# EtherWiz_FullSize.net
KiCad netlist of a schematic drawn in Altium Designer
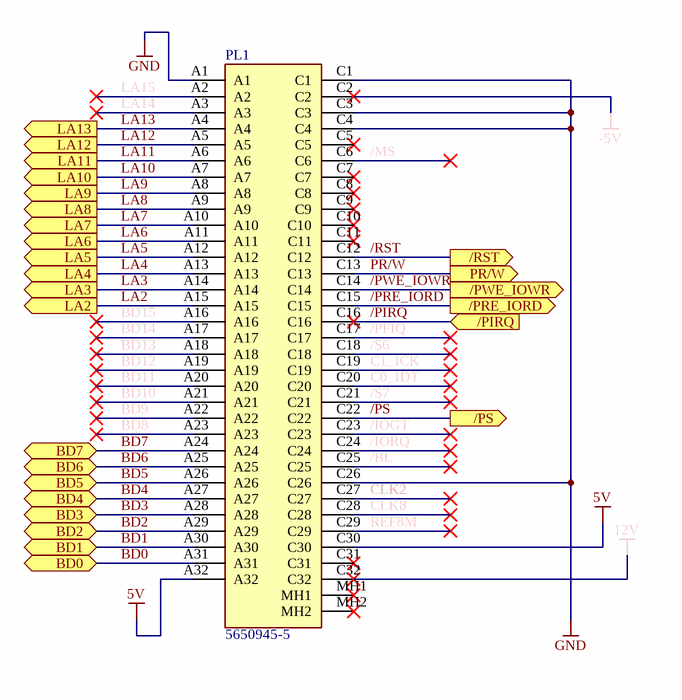
[diagram p0: EtherWiz_FullSize.SchDoc]

(export (version "E")
  (design (tool "Eeschema 10.0.6"))
  (components
    (comp (ref "PL1")
      (value "5650945-5")
      (footprint "SamacSys:56509455")
      (description "Connector")
      (fields (field (name "MOUSER PART NUMBER") "571-5650945-5"))
      (libsource (lib "Acorn") (part "5650945-5"))
    )
  )
  (nets
    (net (code "1") (name "-5V") (class "Default")
      (node (ref "PL1") (pin "C2") (pinfunction "C2_C2") (pintype "passive"))
    )
    (net (code "2") (name "/BD0") (class "Default")
      (node (ref "PL1") (pin "A31") (pinfunction "A31_A31") (pintype "passive"))
    )
    (net (code "3") (name "/BD1") (class "Default")
      (node (ref "PL1") (pin "A30") (pinfunction "A30_A30") (pintype "passive"))
    )
    (net (code "4") (name "/BD2") (class "Default")
      (node (ref "PL1") (pin "A29") (pinfunction "A29_A29") (pintype "passive"))
    )
    (net (code "5") (name "/BD3") (class "Default")
      (node (ref "PL1") (pin "A28") (pinfunction "A28_A28") (pintype "passive"))
    )
    (net (code "6") (name "/BD4") (class "Default")
      (node (ref "PL1") (pin "A27") (pinfunction "A27_A27") (pintype "passive"))
    )
    (net (code "7") (name "/BD5") (class "Default")
      (node (ref "PL1") (pin "A26") (pinfunction "A26_A26") (pintype "passive"))
    )
    (net (code "8") (name "/BD6") (class "Default")
      (node (ref "PL1") (pin "A25") (pinfunction "A25_A25") (pintype "passive"))
    )
    (net (code "9") (name "/BD7") (class "Default")
      (node (ref "PL1") (pin "A24") (pinfunction "A24_A24") (pintype "passive"))
    )
    (net (code "10") (name "/BD8") (class "Default")
      (node (ref "PL1") (pin "A23") (pinfunction "A23_A23") (pintype "passive+no_connect"))
    )
    (net (code "11") (name "/BD9") (class "Default")
      (node (ref "PL1") (pin "A22") (pinfunction "A22_A22") (pintype "passive+no_connect"))
    )
    (net (code "12") (name "/BD10") (class "Default")
      (node (ref "PL1") (pin "A21") (pinfunction "A21_A21") (pintype "passive+no_connect"))
    )
    (net (code "13") (name "/BD11") (class "Default")
      (node (ref "PL1") (pin "A20") (pinfunction "A20_A20") (pintype "passive+no_connect"))
    )
    (net (code "14") (name "/BD12") (class "Default")
      (node (ref "PL1") (pin "A19") (pinfunction "A19_A19") (pintype "passive+no_connect"))
    )
    (net (code "15") (name "/BD13") (class "Default")
      (node (ref "PL1") (pin "A18") (pinfunction "A18_A18") (pintype "passive+no_connect"))
    )
    (net (code "16") (name "/BD14") (class "Default")
      (node (ref "PL1") (pin "A17") (pinfunction "A17_A17") (pintype "passive+no_connect"))
    )
    (net (code "17") (name "/BD15") (class "Default")
      (node (ref "PL1") (pin "A16") (pinfunction "A16_A16") (pintype "passive+no_connect"))
    )
    (net (code "18") (name "/C0_IDT") (class "Default")
      (node (ref "PL1") (pin "C20") (pinfunction "C20_C20") (pintype "passive+no_connect"))
    )
    (net (code "19") (name "/C1_ICK") (class "Default")
      (node (ref "PL1") (pin "C19") (pinfunction "C19_C19") (pintype "passive+no_connect"))
    )
    (net (code "20") (name "/CLK2") (class "Default")
      (node (ref "PL1") (pin "C27") (pinfunction "C27_C27") (pintype "passive+no_connect"))
    )
    (net (code "21") (name "/CLK8") (class "Default")
      (node (ref "PL1") (pin "C28") (pinfunction "C28_C28") (pintype "passive+no_connect"))
    )
    (net (code "22") (name "/LA2") (class "Default")
      (node (ref "PL1") (pin "A15") (pinfunction "A15_A15") (pintype "passive"))
    )
    (net (code "23") (name "/LA3") (class "Default")
      (node (ref "PL1") (pin "A14") (pinfunction "A14_A14") (pintype "passive"))
    )
    (net (code "24") (name "/LA4") (class "Default")
      (node (ref "PL1") (pin "A13") (pinfunction "A13_A13") (pintype "passive"))
    )
    (net (code "25") (name "/LA5") (class "Default")
      (node (ref "PL1") (pin "A12") (pinfunction "A12_A12") (pintype "passive"))
    )
    (net (code "26") (name "/LA6") (class "Default")
      (node (ref "PL1") (pin "A11") (pinfunction "A11_A11") (pintype "passive"))
    )
    (net (code "27") (name "/LA7") (class "Default")
      (node (ref "PL1") (pin "A10") (pinfunction "A10_A10") (pintype "passive"))
    )
    (net (code "28") (name "/LA8") (class "Default")
      (node (ref "PL1") (pin "A9") (pinfunction "A9_A9") (pintype "passive"))
    )
    (net (code "29") (name "/LA9") (class "Default")
      (node (ref "PL1") (pin "A8") (pinfunction "A8_A8") (pintype "passive"))
    )
    (net (code "30") (name "/LA10") (class "Default")
      (node (ref "PL1") (pin "A7") (pinfunction "A7_A7") (pintype "passive"))
    )
    (net (code "31") (name "/LA11") (class "Default")
      (node (ref "PL1") (pin "A6") (pinfunction "A6_A6") (pintype "passive"))
    )
    (net (code "32") (name "/LA12") (class "Default")
      (node (ref "PL1") (pin "A5") (pinfunction "A5_A5") (pintype "passive"))
    )
    (net (code "33") (name "/LA13") (class "Default")
      (node (ref "PL1") (pin "A4") (pinfunction "A4_A4") (pintype "passive"))
    )
    (net (code "34") (name "/LA14") (class "Default")
      (node (ref "PL1") (pin "A3") (pinfunction "A3_A3") (pintype "passive+no_connect"))
    )
    (net (code "35") (name "/LA15") (class "Default")
      (node (ref "PL1") (pin "A2") (pinfunction "A2_A2") (pintype "passive+no_connect"))
    )
    (net (code "36") (name "/PR{slash}W") (class "Default")
      (node (ref "PL1") (pin "C13") (pinfunction "C13_C13") (pintype "passive"))
    )
    (net (code "37") (name "/REF8M") (class "Default")
      (node (ref "PL1") (pin "C29") (pinfunction "C29_C29") (pintype "passive+no_connect"))
    )
    (net (code "38") (name "/{slash}BL") (class "Default")
      (node (ref "PL1") (pin "C25") (pinfunction "C25_C25") (pintype "passive+no_connect"))
    )
    (net (code "39") (name "/{slash}IOGT") (class "Default")
      (node (ref "PL1") (pin "C23") (pinfunction "C23_C23") (pintype "passive+no_connect"))
    )
    (net (code "40") (name "/{slash}IORQ") (class "Default")
      (node (ref "PL1") (pin "C24") (pinfunction "C24_C24") (pintype "passive+no_connect"))
    )
    (net (code "41") (name "/{slash}MS") (class "Default")
      (node (ref "PL1") (pin "C6") (pinfunction "C6_C6") (pintype "passive+no_connect"))
    )
    (net (code "42") (name "/{slash}PFIQ") (class "Default")
      (node (ref "PL1") (pin "C17") (pinfunction "C17_C17") (pintype "passive+no_connect"))
    )
    (net (code "43") (name "/{slash}PIRQ") (class "Default")
      (node (ref "PL1") (pin "C16") (pinfunction "C16_C16") (pintype "passive+no_connect"))
    )
    (net (code "44") (name "/{slash}PRE_IORD") (class "Default")
      (node (ref "PL1") (pin "C15") (pinfunction "C15_C15") (pintype "passive"))
    )
    (net (code "45") (name "/{slash}PS") (class "Default")
      (node (ref "PL1") (pin "C22") (pinfunction "C22_C22") (pintype "passive"))
    )
    (net (code "46") (name "/{slash}PWE_IOWR") (class "Default")
      (node (ref "PL1") (pin "C14") (pinfunction "C14_C14") (pintype "passive"))
    )
    (net (code "47") (name "/{slash}RST") (class "Default")
      (node (ref "PL1") (pin "C12") (pinfunction "C12_C12") (pintype "passive"))
    )
    (net (code "48") (name "/{slash}S6") (class "Default")
      (node (ref "PL1") (pin "C18") (pinfunction "C18_C18") (pintype "passive+no_connect"))
    )
    (net (code "49") (name "/{slash}S7") (class "Default")
      (node (ref "PL1") (pin "C21") (pinfunction "C21_C21") (pintype "passive+no_connect"))
    )
    (net (code "50") (name "5V") (class "Default")
      (node (ref "PL1") (pin "A32") (pinfunction "A32_A32") (pintype "passive"))
      (node (ref "PL1") (pin "C30") (pinfunction "C30_C30") (pintype "passive"))
    )
    (net (code "51") (name "12V") (class "Default")
      (node (ref "PL1") (pin "C32") (pinfunction "C32_C32") (pintype "passive"))
    )
    (net (code "52") (name "GND") (class "Default")
      (node (ref "PL1") (pin "A1") (pinfunction "A1_A1") (pintype "passive"))
      (node (ref "PL1") (pin "C1") (pinfunction "C1_C1") (pintype "passive"))
      (node (ref "PL1") (pin "C26") (pinfunction "C26_C26") (pintype "passive"))
      (node (ref "PL1") (pin "C3") (pinfunction "C3_C3") (pintype "passive"))
      (node (ref "PL1") (pin "C4") (pinfunction "C4_C4") (pintype "passive"))
    )
    (net (code "53") (name "unconnected-(PL1-PadC5)") (class "Default")
      (node (ref "PL1") (pin "C5") (pinfunction "C5_C5") (pintype "passive+no_connect"))
    )
    (net (code "54") (name "unconnected-(PL1-PadC7)") (class "Default")
      (node (ref "PL1") (pin "C7") (pinfunction "C7_C7") (pintype "passive+no_connect"))
    )
    (net (code "55") (name "unconnected-(PL1-PadC8)") (class "Default")
      (node (ref "PL1") (pin "C8") (pinfunction "C8_C8") (pintype "passive+no_connect"))
    )
    (net (code "56") (name "unconnected-(PL1-PadC9)") (class "Default")
      (node (ref "PL1") (pin "C9") (pinfunction "C9_C9") (pintype "passive+no_connect"))
    )
    (net (code "57") (name "unconnected-(PL1-PadC10)") (class "Default")
      (node (ref "PL1") (pin "C10") (pinfunction "C10_C10") (pintype "passive+no_connect"))
    )
    (net (code "58") (name "unconnected-(PL1-PadC11)") (class "Default")
      (node (ref "PL1") (pin "C11") (pinfunction "C11_C11") (pintype "passive+no_connect"))
    )
    (net (code "59") (name "unconnected-(PL1-PadC31)") (class "Default")
      (node (ref "PL1") (pin "C31") (pinfunction "C31_C31") (pintype "passive+no_connect"))
    )
    (net (code "60") (name "unconnected-(PL1-PadMH1)") (class "Default")
      (node (ref "PL1") (pin "MH1") (pinfunction "MH1_MH1") (pintype "passive+no_connect"))
    )
    (net (code "61") (name "unconnected-(PL1-PadMH2)") (class "Default")
      (node (ref "PL1") (pin "MH2") (pinfunction "MH2_MH2") (pintype "passive+no_connect"))
    )
  )
)
